# MercurialSDR_FPGA_BNK.net
KiCad netlist of a schematic drawn in Altium Designer
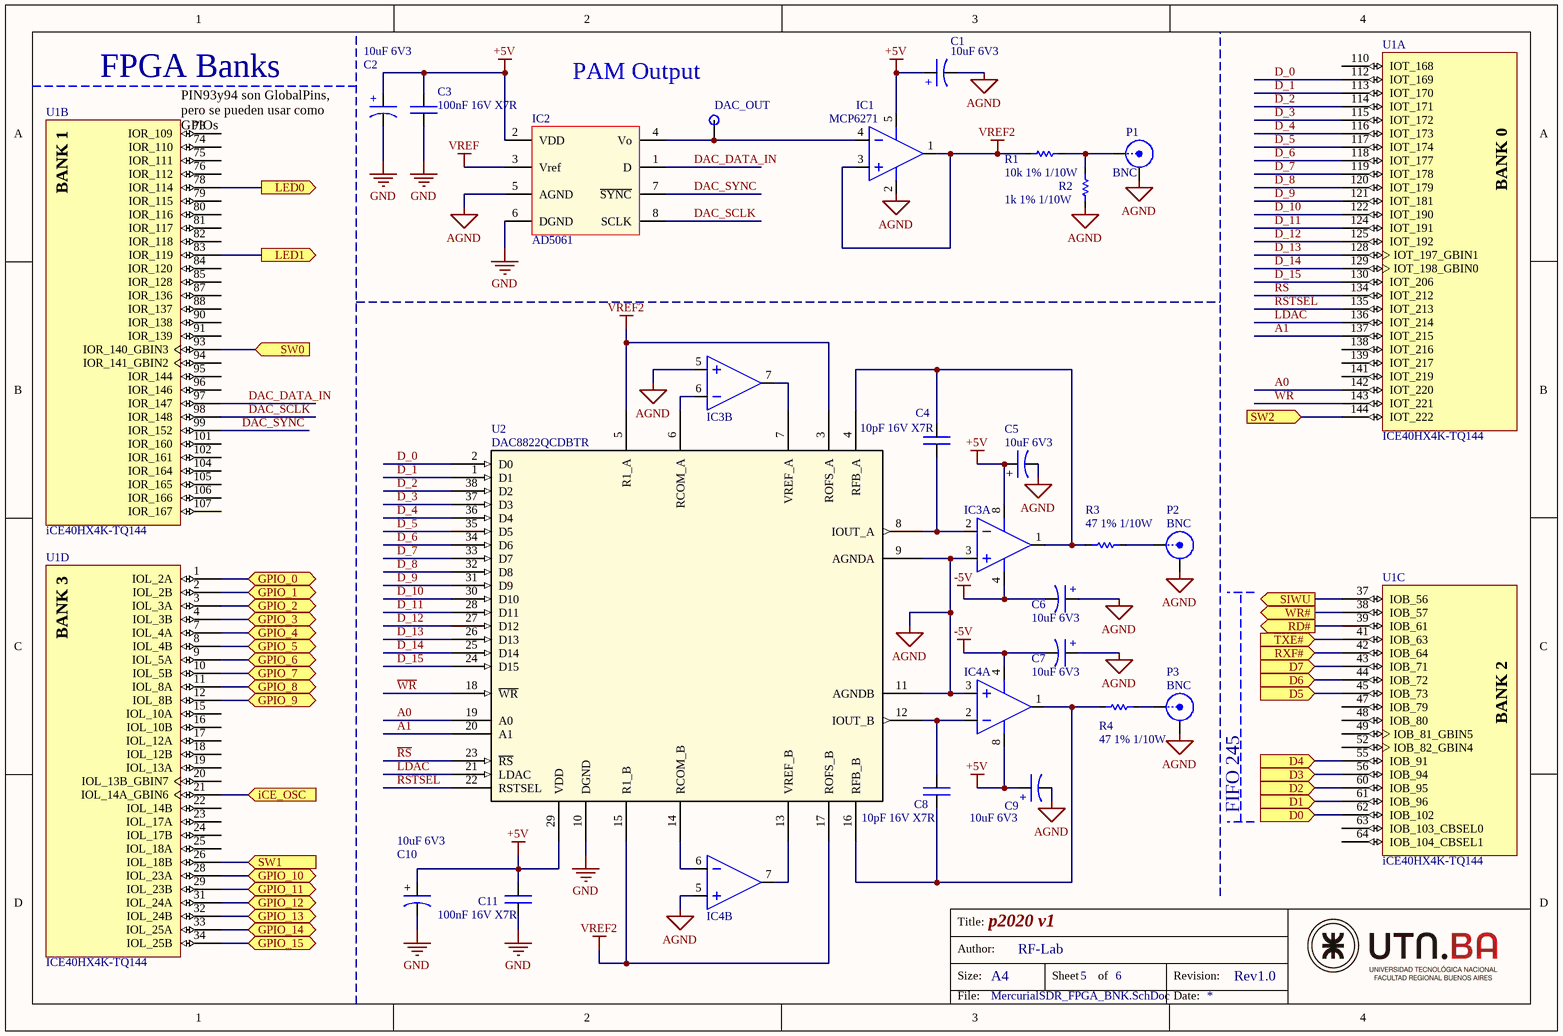
[diagram p0: MercurialSDR_FPGA_BNK.SchDoc]

(export (version "E")
  (design (tool "Eeschema 10.0.6"))
  (components
    (comp (ref "C1")
      (value "10uF 6V3")
      (footprint "CAP_TANT_1206")
      (description "Capacitor polarizado")
      (fields (field (name "Comment") "10uF 6V3 - TAJA106K006RNJ"))
      (libsource (lib "MercurialSDR") (part "Cap Pol"))
    )
    (comp (ref "C2")
      (value "10uF 6V3")
      (footprint "CAP_TANT_1206")
      (description "Capacitor polarizado")
      (fields (field (name "Comment") "10uF 6V3 - TAJA106K006RNJ"))
      (libsource (lib "MercurialSDR") (part "Cap Pol"))
    )
    (comp (ref "C3")
      (value "100nF 16V X7R")
      (footprint "CAP_0603")
      (description "Capacitor no polarizado")
      (fields (field (name "Comment") "100nF 16V X7R - CL10B104KO8NNNC"))
      (libsource (lib "MercurialSDR") (part "Cap"))
    )
    (comp (ref "C4")
      (value "10pF 16V X7R")
      (footprint "CAP_0603")
      (description "Capacitor no polarizado")
      (fields (field (name "Comment") "10pF 16V X7R - C0603C100K4RAC7867"))
      (libsource (lib "MercurialSDR") (part "Cap"))
    )
    (comp (ref "C5")
      (value "10uF 6V3")
      (footprint "CAP_TANT_1206")
      (description "Capacitor polarizado")
      (fields (field (name "Comment") "10uF 6V3 - TAJA106K006RNJ"))
      (libsource (lib "MercurialSDR") (part "Cap Pol"))
    )
    (comp (ref "C6")
      (value "10uF 6V3")
      (footprint "CAP_TANT_1206")
      (description "Capacitor polarizado")
      (fields (field (name "Comment") "10uF 6V3 - TAJA106K006RNJ"))
      (libsource (lib "MercurialSDR") (part "Cap Pol"))
    )
    (comp (ref "C7")
      (value "10uF 6V3")
      (footprint "CAP_TANT_1206")
      (description "Capacitor polarizado")
      (fields (field (name "Comment") "10uF 6V3 - TAJA106K006RNJ"))
      (libsource (lib "MercurialSDR") (part "Cap Pol"))
    )
    (comp (ref "C8")
      (value "10pF 16V X7R")
      (footprint "CAP_0603")
      (description "Capacitor no polarizado")
      (fields (field (name "Comment") "10pF 16V X7R - C0603C100K4RAC7867"))
      (libsource (lib "MercurialSDR") (part "Cap"))
    )
    (comp (ref "C9")
      (value "10uF 6V3")
      (footprint "CAP_TANT_1206")
      (description "Capacitor polarizado")
      (fields (field (name "Comment") "10uF 6V3 - TAJA106K006RNJ"))
      (libsource (lib "MercurialSDR") (part "Cap Pol"))
    )
    (comp (ref "C10")
      (value "10uF 6V3")
      (footprint "CAP_TANT_1206")
      (description "Capacitor polarizado")
      (fields (field (name "Comment") "10uF 6V3 - TAJA106K006RNJ"))
      (libsource (lib "MercurialSDR") (part "Cap Pol"))
    )
    (comp (ref "C11")
      (value "100nF 16V X7R")
      (footprint "CAP_0603")
      (description "Capacitor no polarizado")
      (fields (field (name "Comment") "100nF 16V X7R - CL10B104KO8NNNC"))
      (libsource (lib "MercurialSDR") (part "Cap"))
    )
    (comp (ref "IC1")
      (value "MCP6271 SOT-23-5")
      (footprint "SOT-23-5")
      (description "Operational Amplifier")
      (fields (field (name "PART NUMBER") "MCP6271"))
      (libsource (lib "MercurialSDR") (part "MCP6271T-E/OT"))
    )
    (comp (ref "IC2")
      (value "AD5061")
      (footprint "SOT-23-8")
      (description "DAC SPI")
      (libsource (lib "MercurialSDR") (part "AD5061"))
    )
    (comp (ref "IC3")
      (value "OPAMP2277 - OPA2277UA/2K5")
      (footprint "opa2277")
      (description "Operational Amplifier")
      (libsource (lib "MercurialSDR") (part "OPAMP2277"))
    )
    (comp (ref "IC4")
      (value "OPAMP2277 - OPA2277UA/2K5")
      (footprint "opa2277")
      (description "Operational Amplifier")
      (libsource (lib "MercurialSDR") (part "OPAMP2277"))
    )
    (comp (ref "P1")
      (value "BNC")
      (footprint "CONN_73138-5033_")
      (description "BNC Elbow Connector")
      (fields (field (name "Comment") "0731385033") (field (name "PUBLISHER") "Altium Limited"))
      (libsource (lib "Miscellaneous Connectors") (part "BNC"))
    )
    (comp (ref "P2")
      (value "BNC")
      (footprint "CONN_73138-5033_")
      (description "BNC Elbow Connector")
      (fields (field (name "Comment") "0731385033") (field (name "PUBLISHER") "Altium Limited"))
      (libsource (lib "Miscellaneous Connectors") (part "BNC"))
    )
    (comp (ref "P3")
      (value "BNC")
      (footprint "CONN_73138-5033_")
      (description "BNC Elbow Connector")
      (fields (field (name "Comment") "0731385033") (field (name "PUBLISHER") "Altium Limited"))
      (libsource (lib "Miscellaneous Connectors") (part "BNC"))
    )
    (comp (ref "R1")
      (value "10k 1% 1/10W")
      (footprint "RES_0603")
      (description "Resistor")
      (fields (field (name "Comment") "10k 1% 1/10W - CR0603-FX-1002EAS"))
      (libsource (lib "MercurialSDR") (part "Res"))
    )
    (comp (ref "R2")
      (value "1k 1% 1/10W")
      (footprint "RES_0603")
      (description "Resistor")
      (fields (field (name "Comment") "1k 1% 1/10W - CR0603-FX-1001ELF"))
      (libsource (lib "MercurialSDR") (part "Res"))
    )
    (comp (ref "R3")
      (value "47 1% 1/10W")
      (footprint "RES_0603")
      (description "Resistor")
      (fields (field (name "Comment") "47 1% 1/10W - CR0603-FX-47R0ELF"))
      (libsource (lib "MercurialSDR") (part "Res"))
    )
    (comp (ref "R4")
      (value "47 1% 1/10W")
      (footprint "RES_0603")
      (description "Resistor")
      (fields (field (name "Comment") "47 1% 1/10W - CR0603-FX-47R0ELF"))
      (libsource (lib "MercurialSDR") (part "Res"))
    )
    (comp (ref "TP1")
      (value "Test Point")
      (footprint "TP_TH")
      (fields (field (name "TP NAME") "DAC_OUT"))
      (libsource (lib "MercurialSDR") (part "Test Point"))
    )
    (comp (ref "U1")
      (value "ICE40HX4K-TQ144")
      (footprint "LATC-TQFP-144_L")
      (fields
        (field (name "MANUFACTURER") "Lattice Semiconductor")
        (field (name "PARTNUMBER") "ICE40HX4K-TQ144")
      )
      (libsource (lib "MercurialSDR") (part "ICE40HX4K-TQ144"))
    )
    (comp (ref "U2")
      (value "DAC8822QCDBTR")
      (footprint "dac8822")
      (description "16-Bit, Dual, Parallel Input, Multiplying DAC")
      (fields (field (name "COPYRIGHT") "Copyright (C) 2018 Accelerated Designs. All rights reserved"))
      (libsource (lib "MercurialSDR") (part "DAC8822QCDBTR"))
    )
  )
  (nets
    (net (code "1") (name "+5V") (class "Default")
      (node (ref "C1") (pin "1") (pinfunction "1_1") (pintype "passive"))
      (node (ref "C10") (pin "1") (pinfunction "1_1") (pintype "passive"))
      (node (ref "C11") (pin "1") (pinfunction "1_1") (pintype "passive"))
      (node (ref "C2") (pin "1") (pinfunction "1_1") (pintype "passive"))
      (node (ref "C3") (pin "1") (pinfunction "1_1") (pintype "passive"))
      (node (ref "C5") (pin "1") (pinfunction "1_1") (pintype "passive"))
      (node (ref "C9") (pin "1") (pinfunction "1_1") (pintype "passive"))
      (node (ref "IC1") (pin "5") (pinfunction "Vs+_5") (pintype "passive"))
      (node (ref "IC2") (pin "2") (pinfunction "VDD_2") (pintype "passive"))
      (node (ref "IC3") (pin "8") (pinfunction "Vs+_8") (pintype "passive"))
      (node (ref "IC4") (pin "8") (pinfunction "Vs+_8") (pintype "passive"))
      (node (ref "U2") (pin "29") (pinfunction "VDD_29") (pintype "power_in"))
    )
    (net (code "2") (name "-5V") (class "Default")
      (node (ref "C6") (pin "2") (pinfunction "2_2") (pintype "passive"))
      (node (ref "C7") (pin "2") (pinfunction "2_2") (pintype "passive"))
      (node (ref "IC3") (pin "4") (pinfunction "Vs-_4") (pintype "passive"))
      (node (ref "IC4") (pin "4") (pinfunction "Vs-_4") (pintype "passive"))
    )
    (net (code "3") (name "/A0") (class "Default")
      (node (ref "U1") (pin "142") (pinfunction "IOT_220_142") (pintype "bidirectional"))
      (node (ref "U2") (pin "19") (pinfunction "A0_19") (pintype "passive"))
    )
    (net (code "4") (name "/A1") (class "Default")
      (node (ref "U1") (pin "137") (pinfunction "IOT_215_137") (pintype "bidirectional"))
      (node (ref "U2") (pin "20") (pinfunction "A1_20") (pintype "passive"))
    )
    (net (code "5") (name "/D0") (class "Default")
      (node (ref "U1") (pin "62") (pinfunction "IOB_102_62") (pintype "bidirectional"))
    )
    (net (code "6") (name "/D1") (class "Default")
      (node (ref "U1") (pin "61") (pinfunction "IOB_96_61") (pintype "bidirectional"))
    )
    (net (code "7") (name "/D2") (class "Default")
      (node (ref "U1") (pin "60") (pinfunction "IOB_95_60") (pintype "bidirectional"))
    )
    (net (code "8") (name "/D3") (class "Default")
      (node (ref "U1") (pin "56") (pinfunction "IOB_94_56") (pintype "bidirectional"))
    )
    (net (code "9") (name "/D4") (class "Default")
      (node (ref "U1") (pin "55") (pinfunction "IOB_91_55") (pintype "bidirectional"))
    )
    (net (code "10") (name "/D5") (class "Default")
      (node (ref "U1") (pin "45") (pinfunction "IOB_73_45") (pintype "bidirectional"))
    )
    (net (code "11") (name "/D6") (class "Default")
      (node (ref "U1") (pin "44") (pinfunction "IOB_72_44") (pintype "bidirectional"))
    )
    (net (code "12") (name "/D7") (class "Default")
      (node (ref "U1") (pin "43") (pinfunction "IOB_71_43") (pintype "bidirectional"))
    )
    (net (code "13") (name "/DAC_DATA_IN") (class "Default")
      (node (ref "IC2") (pin "1") (pinfunction "D_1") (pintype "passive"))
      (node (ref "U1") (pin "97") (pinfunction "IOR_147_97") (pintype "bidirectional"))
    )
    (net (code "14") (name "/DAC_SCLK") (class "Default")
      (node (ref "IC2") (pin "8") (pinfunction "SCLK_8") (pintype "passive"))
      (node (ref "U1") (pin "98") (pinfunction "IOR_148_98") (pintype "bidirectional"))
    )
    (net (code "15") (name "/DAC_SYNC") (class "Default")
      (node (ref "IC2") (pin "7") (pinfunction "~{SYNC}_7") (pintype "passive"))
      (node (ref "U1") (pin "99") (pinfunction "IOR_152_99") (pintype "bidirectional"))
    )
    (net (code "16") (name "/D_0") (class "Default")
      (node (ref "U1") (pin "112") (pinfunction "IOT_169_112") (pintype "bidirectional"))
      (node (ref "U2") (pin "2") (pinfunction "D0_2") (pintype "input"))
    )
    (net (code "17") (name "/D_1") (class "Default")
      (node (ref "U1") (pin "113") (pinfunction "IOT_170_113") (pintype "bidirectional"))
      (node (ref "U2") (pin "1") (pinfunction "D1_1") (pintype "input"))
    )
    (net (code "18") (name "/D_2") (class "Default")
      (node (ref "U1") (pin "114") (pinfunction "IOT_171_114") (pintype "bidirectional"))
      (node (ref "U2") (pin "38") (pinfunction "D2_38") (pintype "input"))
    )
    (net (code "19") (name "/D_3") (class "Default")
      (node (ref "U1") (pin "115") (pinfunction "IOT_172_115") (pintype "bidirectional"))
      (node (ref "U2") (pin "37") (pinfunction "D3_37") (pintype "input"))
    )
    (net (code "20") (name "/D_4") (class "Default")
      (node (ref "U1") (pin "116") (pinfunction "IOT_173_116") (pintype "bidirectional"))
      (node (ref "U2") (pin "36") (pinfunction "D4_36") (pintype "input"))
    )
    (net (code "21") (name "/D_5") (class "Default")
      (node (ref "U1") (pin "117") (pinfunction "IOT_174_117") (pintype "bidirectional"))
      (node (ref "U2") (pin "35") (pinfunction "D5_35") (pintype "input"))
    )
    (net (code "22") (name "/D_6") (class "Default")
      (node (ref "U1") (pin "118") (pinfunction "IOT_177_118") (pintype "bidirectional"))
      (node (ref "U2") (pin "34") (pinfunction "D6_34") (pintype "input"))
    )
    (net (code "23") (name "/D_7") (class "Default")
      (node (ref "U1") (pin "119") (pinfunction "IOT_178_119") (pintype "bidirectional"))
      (node (ref "U2") (pin "33") (pinfunction "D7_33") (pintype "input"))
    )
    (net (code "24") (name "/D_8") (class "Default")
      (node (ref "U1") (pin "120") (pinfunction "IOT_179_120") (pintype "bidirectional"))
      (node (ref "U2") (pin "32") (pinfunction "D8_32") (pintype "input"))
    )
    (net (code "25") (name "/D_9") (class "Default")
      (node (ref "U1") (pin "121") (pinfunction "IOT_181_121") (pintype "bidirectional"))
      (node (ref "U2") (pin "31") (pinfunction "D9_31") (pintype "input"))
    )
    (net (code "26") (name "/D_10") (class "Default")
      (node (ref "U1") (pin "122") (pinfunction "IOT_190_122") (pintype "bidirectional"))
      (node (ref "U2") (pin "30") (pinfunction "D10_30") (pintype "input"))
    )
    (net (code "27") (name "/D_11") (class "Default")
      (node (ref "U1") (pin "124") (pinfunction "IOT_191_124") (pintype "bidirectional"))
      (node (ref "U2") (pin "28") (pinfunction "D11_28") (pintype "input"))
    )
    (net (code "28") (name "/D_12") (class "Default")
      (node (ref "U1") (pin "125") (pinfunction "IOT_192_125") (pintype "bidirectional"))
      (node (ref "U2") (pin "27") (pinfunction "D12_27") (pintype "input"))
    )
    (net (code "29") (name "/D_13") (class "Default")
      (node (ref "U1") (pin "128") (pinfunction "IOT_197_GBIN1_128") (pintype "bidirectional"))
      (node (ref "U2") (pin "26") (pinfunction "D13_26") (pintype "input"))
    )
    (net (code "30") (name "/D_14") (class "Default")
      (node (ref "U1") (pin "129") (pinfunction "IOT_198_GBIN0_129") (pintype "bidirectional"))
      (node (ref "U2") (pin "25") (pinfunction "D14_25") (pintype "input"))
    )
    (net (code "31") (name "/D_15") (class "Default")
      (node (ref "U1") (pin "130") (pinfunction "IOT_206_130") (pintype "bidirectional"))
      (node (ref "U2") (pin "24") (pinfunction "D15_24") (pintype "input"))
    )
    (net (code "32") (name "/GPIO_0") (class "Default")
      (node (ref "U1") (pin "1") (pinfunction "IOL_2A_1") (pintype "bidirectional"))
    )
    (net (code "33") (name "/GPIO_1") (class "Default")
      (node (ref "U1") (pin "2") (pinfunction "IOL_2B_2") (pintype "bidirectional"))
    )
    (net (code "34") (name "/GPIO_2") (class "Default")
      (node (ref "U1") (pin "3") (pinfunction "IOL_3A_3") (pintype "bidirectional"))
    )
    (net (code "35") (name "/GPIO_3") (class "Default")
      (node (ref "U1") (pin "4") (pinfunction "IOL_3B_4") (pintype "bidirectional"))
    )
    (net (code "36") (name "/GPIO_4") (class "Default")
      (node (ref "U1") (pin "7") (pinfunction "IOL_4A_7") (pintype "bidirectional"))
    )
    (net (code "37") (name "/GPIO_5") (class "Default")
      (node (ref "U1") (pin "8") (pinfunction "IOL_4B_8") (pintype "bidirectional"))
    )
    (net (code "38") (name "/GPIO_6") (class "Default")
      (node (ref "U1") (pin "9") (pinfunction "IOL_5A_9") (pintype "bidirectional"))
    )
    (net (code "39") (name "/GPIO_7") (class "Default")
      (node (ref "U1") (pin "10") (pinfunction "IOL_5B_10") (pintype "bidirectional"))
    )
    (net (code "40") (name "/GPIO_8") (class "Default")
      (node (ref "U1") (pin "11") (pinfunction "IOL_8A_11") (pintype "bidirectional"))
    )
    (net (code "41") (name "/GPIO_9") (class "Default")
      (node (ref "U1") (pin "12") (pinfunction "IOL_8B_12") (pintype "bidirectional"))
    )
    (net (code "42") (name "/GPIO_10") (class "Default")
      (node (ref "U1") (pin "28") (pinfunction "IOL_23A_28") (pintype "bidirectional"))
    )
    (net (code "43") (name "/GPIO_11") (class "Default")
      (node (ref "U1") (pin "29") (pinfunction "IOL_23B_29") (pintype "bidirectional"))
    )
    (net (code "44") (name "/GPIO_12") (class "Default")
      (node (ref "U1") (pin "31") (pinfunction "IOL_24A_31") (pintype "bidirectional"))
    )
    (net (code "45") (name "/GPIO_13") (class "Default")
      (node (ref "U1") (pin "32") (pinfunction "IOL_24B_32") (pintype "bidirectional"))
    )
    (net (code "46") (name "/GPIO_14") (class "Default")
      (node (ref "U1") (pin "33") (pinfunction "IOL_25A_33") (pintype "bidirectional"))
    )
    (net (code "47") (name "/GPIO_15") (class "Default")
      (node (ref "U1") (pin "34") (pinfunction "IOL_25B_34") (pintype "bidirectional"))
    )
    (net (code "48") (name "/LDAC") (class "Default")
      (node (ref "U1") (pin "136") (pinfunction "IOT_214_136") (pintype "bidirectional"))
      (node (ref "U2") (pin "21") (pinfunction "LDAC_21") (pintype "input"))
    )
    (net (code "49") (name "/LED0") (class "Default")
      (node (ref "U1") (pin "78") (pinfunction "IOR_114_78") (pintype "bidirectional"))
    )
    (net (code "50") (name "/LED1") (class "Default")
      (node (ref "U1") (pin "83") (pinfunction "IOR_119_83") (pintype "bidirectional"))
    )
    (net (code "51") (name "/RD#") (class "Default")
      (node (ref "U1") (pin "39") (pinfunction "IOB_61_39") (pintype "bidirectional"))
    )
    (net (code "52") (name "/RSTSEL") (class "Default")
      (node (ref "U1") (pin "135") (pinfunction "IOT_213_135") (pintype "bidirectional"))
      (node (ref "U2") (pin "22") (pinfunction "RSTSEL_22") (pintype "passive"))
    )
    (net (code "53") (name "/RXF#") (class "Default")
      (node (ref "U1") (pin "42") (pinfunction "IOB_64_42") (pintype "bidirectional"))
    )
    (net (code "54") (name "/SIWU") (class "Default")
      (node (ref "U1") (pin "37") (pinfunction "IOB_56_37") (pintype "bidirectional"))
    )
    (net (code "55") (name "/SW0") (class "Default")
      (node (ref "U1") (pin "93") (pinfunction "IOR_140_GBIN3_93") (pintype "bidirectional"))
    )
    (net (code "56") (name "/SW1") (class "Default")
      (node (ref "U1") (pin "26") (pinfunction "IOL_18B_26") (pintype "bidirectional"))
    )
    (net (code "57") (name "/SW2") (class "Default")
      (node (ref "U1") (pin "144") (pinfunction "IOT_222_144") (pintype "bidirectional"))
    )
    (net (code "58") (name "/TXE#") (class "Default")
      (node (ref "U1") (pin "41") (pinfunction "IOB_63_41") (pintype "bidirectional"))
    )
    (net (code "59") (name "/WR#") (class "Default")
      (node (ref "U1") (pin "38") (pinfunction "IOB_57_38") (pintype "bidirectional"))
    )
    (net (code "60") (name "/iCE_OSC") (class "Default")
      (node (ref "U1") (pin "21") (pinfunction "IOL_14A_GBIN6_21") (pintype "bidirectional"))
    )
    (net (code "61") (name "/~{RS}") (class "Default")
      (node (ref "U1") (pin "134") (pinfunction "IOT_212_134") (pintype "bidirectional"))
      (node (ref "U2") (pin "23") (pinfunction "~{RS}_23") (pintype "input"))
    )
    (net (code "62") (name "/~{WR}") (class "Default")
      (node (ref "U1") (pin "143") (pinfunction "IOT_221_143") (pintype "bidirectional"))
      (node (ref "U2") (pin "18") (pinfunction "~{WR}_18") (pintype "input"))
    )
    (net (code "63") (name "AGND") (class "Default")
      (node (ref "C1") (pin "2") (pinfunction "2_2") (pintype "passive"))
      (node (ref "C5") (pin "2") (pinfunction "2_2") (pintype "passive"))
      (node (ref "C6") (pin "1") (pinfunction "1_1") (pintype "passive"))
      (node (ref "C7") (pin "1") (pinfunction "1_1") (pintype "passive"))
      (node (ref "C9") (pin "2") (pinfunction "2_2") (pintype "passive"))
      (node (ref "IC1") (pin "2") (pinfunction "Vs-_2") (pintype "passive"))
      (node (ref "IC2") (pin "5") (pinfunction "AGND_5") (pintype "passive"))
      (node (ref "IC3") (pin "3") (pinfunction "V+_3") (pintype "passive"))
      (node (ref "IC3") (pin "5") (pinfunction "V+_5") (pintype "passive"))
      (node (ref "IC4") (pin "3") (pinfunction "V+_3") (pintype "passive"))
      (node (ref "IC4") (pin "5") (pinfunction "V+_5") (pintype "passive"))
      (node (ref "P1") (pin "2") (pinfunction "Y_2") (pintype "passive"))
      (node (ref "P2") (pin "2") (pinfunction "Y_2") (pintype "passive"))
      (node (ref "P3") (pin "2") (pinfunction "Y_2") (pintype "passive"))
      (node (ref "R2") (pin "2") (pinfunction "2_2") (pintype "passive"))
      (node (ref "U2") (pin "11") (pinfunction "AGNDB_11") (pintype "passive"))
      (node (ref "U2") (pin "9") (pinfunction "AGNDA_9") (pintype "passive"))
    )
    (net (code "64") (name "GND") (class "Default")
      (node (ref "C10") (pin "2") (pinfunction "2_2") (pintype "passive"))
      (node (ref "C11") (pin "2") (pinfunction "2_2") (pintype "passive"))
      (node (ref "C2") (pin "2") (pinfunction "2_2") (pintype "passive"))
      (node (ref "C3") (pin "2") (pinfunction "2_2") (pintype "passive"))
      (node (ref "IC2") (pin "6") (pinfunction "DGND_6") (pintype "passive"))
      (node (ref "U2") (pin "10") (pinfunction "DGND_10") (pintype "power_in"))
    )
    (net (code "65") (name "Net-(IC1-V-)") (class "Default")
      (node (ref "IC1") (pin "4") (pinfunction "V-_4") (pintype "passive"))
      (node (ref "IC2") (pin "4") (pinfunction "Vo_4") (pintype "passive"))
      (node (ref "TP1") (pin "1") (pinfunction "TP?_1") (pintype "passive"))
    )
    (net (code "66") (name "Net-(IC3A-V-)") (class "Default")
      (node (ref "C4") (pin "2") (pinfunction "2_2") (pintype "passive"))
      (node (ref "IC3") (pin "2") (pinfunction "V-_2") (pintype "passive"))
      (node (ref "U2") (pin "8") (pinfunction "IOUT_A_8") (pintype "output"))
    )
    (net (code "67") (name "Net-(IC3A-Vo)") (class "Default")
      (node (ref "C4") (pin "1") (pinfunction "1_1") (pintype "passive"))
      (node (ref "IC3") (pin "1") (pinfunction "Vo_1") (pintype "passive"))
      (node (ref "R3") (pin "1") (pinfunction "1_1") (pintype "passive"))
      (node (ref "U2") (pin "4") (pinfunction "RFB_A_4") (pintype "passive"))
    )
    (net (code "68") (name "Net-(IC3B-V-)") (class "Default")
      (node (ref "IC3") (pin "6") (pinfunction "V-_6") (pintype "passive"))
      (node (ref "U2") (pin "6") (pinfunction "RCOM_A_6") (pintype "passive"))
    )
    (net (code "69") (name "Net-(IC3B-Vo)") (class "Default")
      (node (ref "IC3") (pin "7") (pinfunction "Vo_7") (pintype "passive"))
      (node (ref "U2") (pin "7") (pinfunction "VREF_A_7") (pintype "power_in"))
    )
    (net (code "70") (name "Net-(IC4A-V-)") (class "Default")
      (node (ref "C8") (pin "1") (pinfunction "1_1") (pintype "passive"))
      (node (ref "IC4") (pin "2") (pinfunction "V-_2") (pintype "passive"))
      (node (ref "U2") (pin "12") (pinfunction "IOUT_B_12") (pintype "output"))
    )
    (net (code "71") (name "Net-(IC4A-Vo)") (class "Default")
      (node (ref "C8") (pin "2") (pinfunction "2_2") (pintype "passive"))
      (node (ref "IC4") (pin "1") (pinfunction "Vo_1") (pintype "passive"))
      (node (ref "R4") (pin "1") (pinfunction "1_1") (pintype "passive"))
      (node (ref "U2") (pin "16") (pinfunction "RFB_B_16") (pintype "passive"))
    )
    (net (code "72") (name "Net-(IC4B-V-)") (class "Default")
      (node (ref "IC4") (pin "6") (pinfunction "V-_6") (pintype "passive"))
      (node (ref "U2") (pin "14") (pinfunction "RCOM_B_14") (pintype "passive"))
    )
    (net (code "73") (name "Net-(IC4B-Vo)") (class "Default")
      (node (ref "IC4") (pin "7") (pinfunction "Vo_7") (pintype "passive"))
      (node (ref "U2") (pin "13") (pinfunction "VREF_B_13") (pintype "power_in"))
    )
    (net (code "74") (name "Net-(P1-X)") (class "Default")
      (node (ref "P1") (pin "1") (pinfunction "X_1") (pintype "passive"))
      (node (ref "R1") (pin "2") (pinfunction "2_2") (pintype "passive"))
      (node (ref "R2") (pin "1") (pinfunction "1_1") (pintype "passive"))
    )
    (net (code "75") (name "Net-(P2-X)") (class "Default")
      (node (ref "P2") (pin "1") (pinfunction "X_1") (pintype "passive"))
      (node (ref "R3") (pin "2") (pinfunction "2_2") (pintype "passive"))
    )
    (net (code "76") (name "Net-(P3-X)") (class "Default")
      (node (ref "P3") (pin "1") (pinfunction "X_1") (pintype "passive"))
      (node (ref "R4") (pin "2") (pinfunction "2_2") (pintype "passive"))
    )
    (net (code "77") (name "VREF") (class "Default")
      (node (ref "IC2") (pin "3") (pinfunction "Vref_3") (pintype "passive"))
    )
    (net (code "78") (name "VREF2") (class "Default")
      (node (ref "IC1") (pin "1") (pinfunction "Vo_1") (pintype "passive"))
      (node (ref "IC1") (pin "3") (pinfunction "V+_3") (pintype "passive"))
      (node (ref "R1") (pin "1") (pinfunction "1_1") (pintype "passive"))
      (node (ref "U2") (pin "15") (pinfunction "R1_B_15") (pintype "passive"))
      (node (ref "U2") (pin "17") (pinfunction "ROFS_B_17") (pintype "passive"))
      (node (ref "U2") (pin "3") (pinfunction "ROFS_A_3") (pintype "passive"))
      (node (ref "U2") (pin "5") (pinfunction "R1_A_5") (pintype "passive"))
    )
    (net (code "79") (name "unconnected-(U1A-IOT_168-Pad110)") (class "Default")
      (node (ref "U1") (pin "110") (pinfunction "IOT_168_110") (pintype "bidirectional"))
    )
    (net (code "80") (name "unconnected-(U1A-IOT_216-Pad138)") (class "Default")
      (node (ref "U1") (pin "138") (pinfunction "IOT_216_138") (pintype "bidirectional"))
    )
    (net (code "81") (name "unconnected-(U1A-IOT_217-Pad139)") (class "Default")
      (node (ref "U1") (pin "139") (pinfunction "IOT_217_139") (pintype "bidirectional"))
    )
    (net (code "82") (name "unconnected-(U1A-IOT_219-Pad141)") (class "Default")
      (node (ref "U1") (pin "141") (pinfunction "IOT_219_141") (pintype "bidirectional"))
    )
    (net (code "83") (name "unconnected-(U1B-IOR_109-Pad73)") (class "Default")
      (node (ref "U1") (pin "73") (pinfunction "IOR_109_73") (pintype "bidirectional"))
    )
    (net (code "84") (name "unconnected-(U1B-IOR_110-Pad74)") (class "Default")
      (node (ref "U1") (pin "74") (pinfunction "IOR_110_74") (pintype "bidirectional"))
    )
    (net (code "85") (name "unconnected-(U1B-IOR_111-Pad75)") (class "Default")
      (node (ref "U1") (pin "75") (pinfunction "IOR_111_75") (pintype "bidirectional"))
    )
    (net (code "86") (name "unconnected-(U1B-IOR_112-Pad76)") (class "Default")
      (node (ref "U1") (pin "76") (pinfunction "IOR_112_76") (pintype "bidirectional"))
    )
    (net (code "87") (name "unconnected-(U1B-IOR_115-Pad79)") (class "Default")
      (node (ref "U1") (pin "79") (pinfunction "IOR_115_79") (pintype "bidirectional"))
    )
    (net (code "88") (name "unconnected-(U1B-IOR_116-Pad80)") (class "Default")
      (node (ref "U1") (pin "80") (pinfunction "IOR_116_80") (pintype "bidirectional"))
    )
    (net (code "89") (name "unconnected-(U1B-IOR_117-Pad81)") (class "Default")
      (node (ref "U1") (pin "81") (pinfunction "IOR_117_81") (pintype "bidirectional"))
    )
    (net (code "90") (name "unconnected-(U1B-IOR_118-Pad82)") (class "Default")
      (node (ref "U1") (pin "82") (pinfunction "IOR_118_82") (pintype "bidirectional"))
    )
    (net (code "91") (name "unconnected-(U1B-IOR_120-Pad84)") (class "Default")
      (node (ref "U1") (pin "84") (pinfunction "IOR_120_84") (pintype "bidirectional"))
    )
    (net (code "92") (name "unconnected-(U1B-IOR_128-Pad85)") (class "Default")
      (node (ref "U1") (pin "85") (pinfunction "IOR_128_85") (pintype "bidirectional"))
    )
    (net (code "93") (name "unconnected-(U1B-IOR_136-Pad87)") (class "Default")
      (node (ref "U1") (pin "87") (pinfunction "IOR_136_87") (pintype "bidirectional"))
    )
    (net (code "94") (name "unconnected-(U1B-IOR_137-Pad88)") (class "Default")
      (node (ref "U1") (pin "88") (pinfunction "IOR_137_88") (pintype "bidirectional"))
    )
    (net (code "95") (name "unconnected-(U1B-IOR_138-Pad90)") (class "Default")
      (node (ref "U1") (pin "90") (pinfunction "IOR_138_90") (pintype "bidirectional"))
    )
    (net (code "96") (name "unconnected-(U1B-IOR_139-Pad91)") (class "Default")
      (node (ref "U1") (pin "91") (pinfunction "IOR_139_91") (pintype "bidirectional"))
    )
    (net (code "97") (name "unconnected-(U1B-IOR_141_GBIN2-Pad94)") (class "Default")
      (node (ref "U1") (pin "94") (pinfunction "IOR_141_GBIN2_94") (pintype "bidirectional"))
    )
    (net (code "98") (name "unconnected-(U1B-IOR_144-Pad95)") (class "Default")
      (node (ref "U1") (pin "95") (pinfunction "IOR_144_95") (pintype "bidirectional"))
    )
    (net (code "99") (name "unconnected-(U1B-IOR_146-Pad96)") (class "Default")
      (node (ref "U1") (pin "96") (pinfunction "IOR_146_96") (pintype "bidirectional"))
    )
    (net (code "100") (name "unconnected-(U1B-IOR_160-Pad101)") (class "Default")
      (node (ref "U1") (pin "101") (pinfunction "IOR_160_101") (pintype "bidirectional"))
    )
    (net (code "101") (name "unconnected-(U1B-IOR_161-Pad102)") (class "Default")
      (node (ref "U1") (pin "102") (pinfunction "IOR_161_102") (pintype "bidirectional"))
    )
    (net (code "102") (name "unconnected-(U1B-IOR_164-Pad104)") (class "Default")
      (node (ref "U1") (pin "104") (pinfunction "IOR_164_104") (pintype "bidirectional"))
    )
    (net (code "103") (name "unconnected-(U1B-IOR_165-Pad105)") (class "Default")
      (node (ref "U1") (pin "105") (pinfunction "IOR_165_105") (pintype "bidirectional"))
    )
    (net (code "104") (name "unconnected-(U1B-IOR_166-Pad106)") (class "Default")
      (node (ref "U1") (pin "106") (pinfunction "IOR_166_106") (pintype "bidirectional"))
    )
    (net (code "105") (name "unconnected-(U1B-IOR_167-Pad107)") (class "Default")
      (node (ref "U1") (pin "107") (pinfunction "IOR_167_107") (pintype "bidirectional"))
    )
    (net (code "106") (name "unconnected-(U1C-IOB_79-Pad47)") (class "Default")
      (node (ref "U1") (pin "47") (pinfunction "IOB_79_47") (pintype "bidirectional"))
    )
    (net (code "107") (name "unconnected-(U1C-IOB_80-Pad48)") (class "Default")
      (node (ref "U1") (pin "48") (pinfunction "IOB_80_48") (pintype "bidirectional"))
    )
    (net (code "108") (name "unconnected-(U1C-IOB_81_GBIN5-Pad49)") (class "Default")
      (node (ref "U1") (pin "49") (pinfunction "IOB_81_GBIN5_49") (pintype "bidirectional"))
    )
    (net (code "109") (name "unconnected-(U1C-IOB_82_GBIN4-Pad52)") (class "Default")
      (node (ref "U1") (pin "52") (pinfunction "IOB_82_GBIN4_52") (pintype "bidirectional"))
    )
    (net (code "110") (name "unconnected-(U1C-IOB_103_CBSEL0-Pad63)") (class "Default")
      (node (ref "U1") (pin "63") (pinfunction "IOB_103_CBSEL0_63") (pintype "bidirectional"))
    )
    (net (code "111") (name "unconnected-(U1C-IOB_104_CBSEL1-Pad64)") (class "Default")
      (node (ref "U1") (pin "64") (pinfunction "IOB_104_CBSEL1_64") (pintype "bidirectional"))
    )
    (net (code "112") (name "unconnected-(U1D-IOL_10A-Pad15)") (class "Default")
      (node (ref "U1") (pin "15") (pinfunction "IOL_10A_15") (pintype "bidirectional"))
    )
    (net (code "113") (name "unconnected-(U1D-IOL_10B-Pad16)") (class "Default")
      (node (ref "U1") (pin "16") (pinfunction "IOL_10B_16") (pintype "bidirectional"))
    )
    (net (code "114") (name "unconnected-(U1D-IOL_12A-Pad17)") (class "Default")
      (node (ref "U1") (pin "17") (pinfunction "IOL_12A_17") (pintype "bidirectional"))
    )
    (net (code "115") (name "unconnected-(U1D-IOL_12B-Pad18)") (class "Default")
      (node (ref "U1") (pin "18") (pinfunction "IOL_12B_18") (pintype "bidirectional"))
    )
    (net (code "116") (name "unconnected-(U1D-IOL_13A-Pad19)") (class "Default")
      (node (ref "U1") (pin "19") (pinfunction "IOL_13A_19") (pintype "bidirectional"))
    )
    (net (code "117") (name "unconnected-(U1D-IOL_13B_GBIN7-Pad20)") (class "Default")
      (node (ref "U1") (pin "20") (pinfunction "IOL_13B_GBIN7_20") (pintype "bidirectional"))
    )
    (net (code "118") (name "unconnected-(U1D-IOL_14B-Pad22)") (class "Default")
      (node (ref "U1") (pin "22") (pinfunction "IOL_14B_22") (pintype "bidirectional"))
    )
    (net (code "119") (name "unconnected-(U1D-IOL_17A-Pad23)") (class "Default")
      (node (ref "U1") (pin "23") (pinfunction "IOL_17A_23") (pintype "bidirectional"))
    )
    (net (code "120") (name "unconnected-(U1D-IOL_17B-Pad24)") (class "Default")
      (node (ref "U1") (pin "24") (pinfunction "IOL_17B_24") (pintype "bidirectional"))
    )
    (net (code "121") (name "unconnected-(U1D-IOL_18A-Pad25)") (class "Default")
      (node (ref "U1") (pin "25") (pinfunction "IOL_18A_25") (pintype "bidirectional"))
    )
  )
)
